# base_de_tiempos.net
KiCad netlist of a schematic drawn in Altium Designer
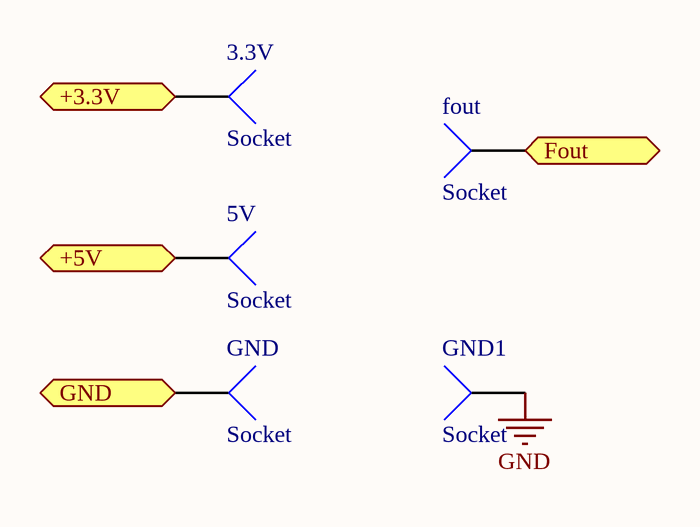
[diagram p0: base de tiempos.SchDoc]

(export (version "E")
  (design (tool "Eeschema 10.0.6"))
  (components
    (comp (ref "3.3V")
      (value "Socket")
      (footprint "PIN1")
      (fields (field (name "PUBLISHER") "Altium Limited"))
      (libsource (lib "Miscellaneous Connectors") (part "Socket"))
    )
    (comp (ref "5V")
      (value "Socket")
      (footprint "PIN1")
      (fields (field (name "PUBLISHER") "Altium Limited"))
      (libsource (lib "Miscellaneous Connectors") (part "Socket"))
    )
    (comp (ref "fout")
      (value "Socket")
      (footprint "PIN1")
      (fields (field (name "PUBLISHER") "Altium Limited"))
      (libsource (lib "Miscellaneous Connectors") (part "Socket"))
    )
    (comp (ref "GND")
      (value "Socket")
      (footprint "PIN1")
      (fields (field (name "PUBLISHER") "Altium Limited"))
      (libsource (lib "Miscellaneous Connectors") (part "Socket"))
    )
    (comp (ref "GND1")
      (value "Socket")
      (footprint "PIN1")
      (fields (field (name "PUBLISHER") "Altium Limited"))
      (libsource (lib "Miscellaneous Connectors") (part "Socket"))
    )
  )
  (nets
    (net (code "1") (name "/+3.3V") (class "Default")
      (node (ref "3.3V") (pin "1") (pinfunction "1_1") (pintype "passive"))
    )
    (net (code "2") (name "/+5V") (class "Default")
      (node (ref "5V") (pin "1") (pinfunction "1_1") (pintype "passive"))
    )
    (net (code "3") (name "/Fout") (class "Default")
      (node (ref "fout") (pin "1") (pinfunction "1_1") (pintype "passive"))
    )
    (net (code "4") (name "GND") (class "Default")
      (node (ref "GND") (pin "1") (pinfunction "1_1") (pintype "passive"))
      (node (ref "GND1") (pin "1") (pinfunction "1_1") (pintype "passive"))
    )
  )
)
